# FluxamasynthPhoton.net
KiCad netlist of a schematic drawn in EAGLE
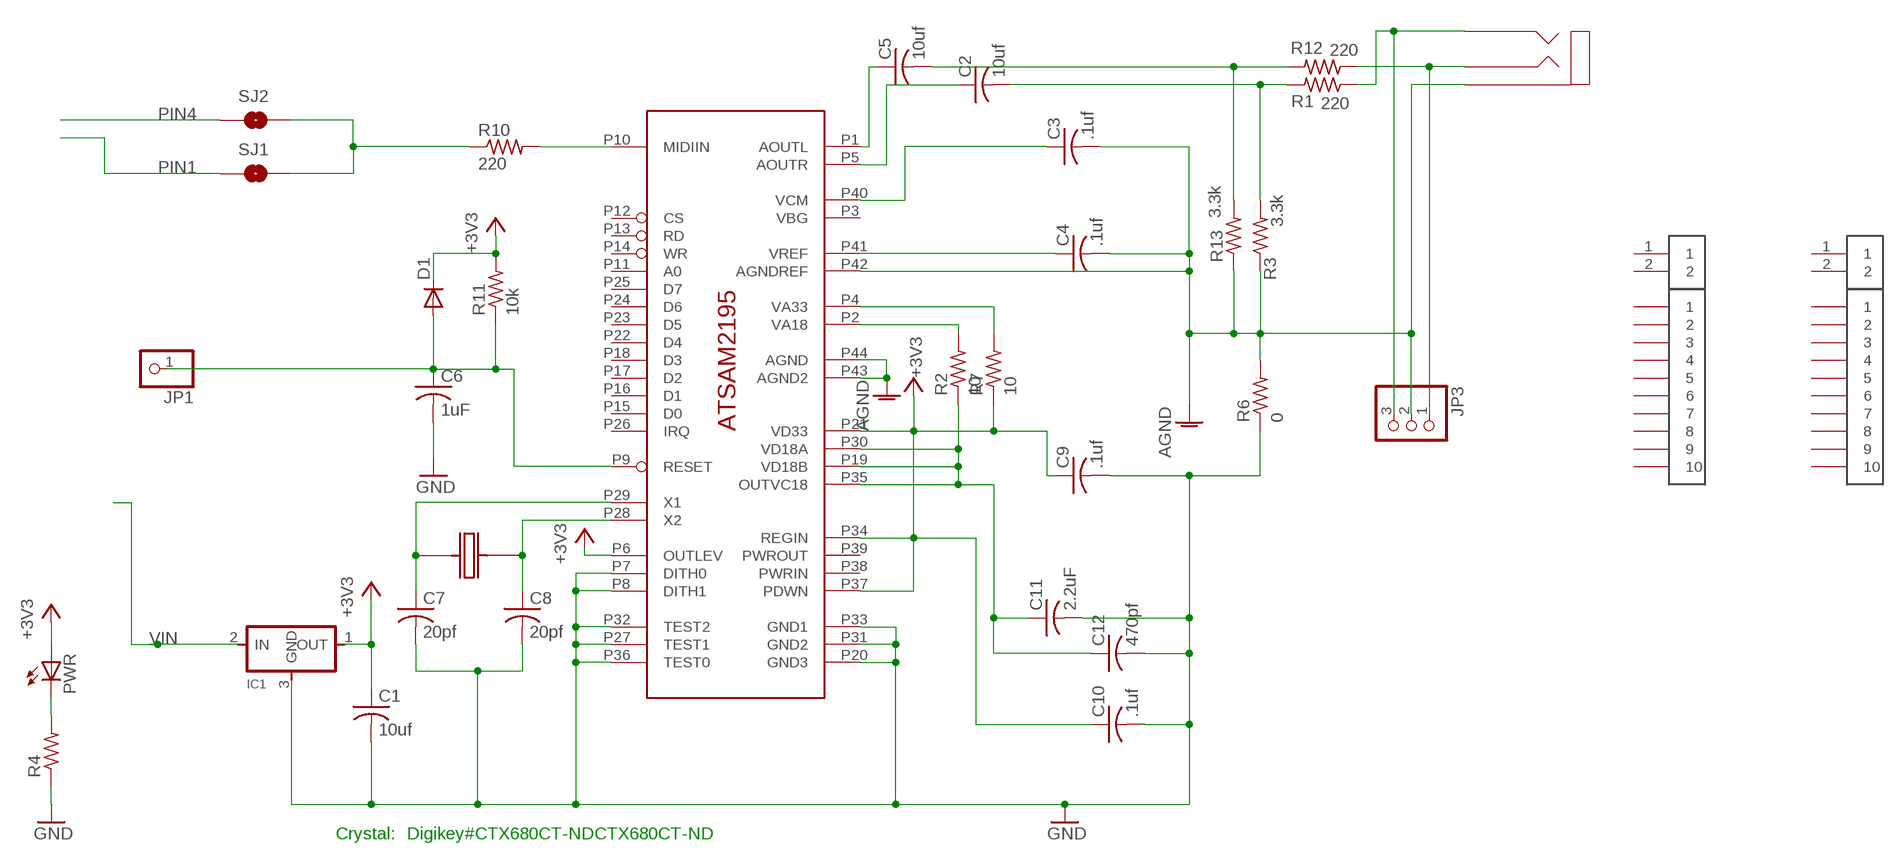
[diagram p0: schematic, sheet 1]

(export (version "E")
  (design (tool "Eeschema 10.0.6"))
  (components
    (comp (ref "C1")
      (value "10uf")
      (footprint "eagle-import:C0603")
      (libsource (lib "eagle-import") (part "C-USC0603"))
    )
    (comp (ref "C2")
      (value "10uf")
      (footprint "eagle-import:C0603")
      (libsource (lib "eagle-import") (part "C-USC0603"))
    )
    (comp (ref "C3")
      (value ".1uf")
      (footprint "eagle-import:C0603")
      (libsource (lib "eagle-import") (part "C-USC0603"))
    )
    (comp (ref "C4")
      (value ".1uf")
      (footprint "eagle-import:C0603")
      (libsource (lib "eagle-import") (part "C-USC0603"))
    )
    (comp (ref "C5")
      (value "10uf")
      (footprint "eagle-import:C0603")
      (libsource (lib "eagle-import") (part "C-USC0603"))
    )
    (comp (ref "C6")
      (value "1uF")
      (footprint "eagle-import:C0603")
      (libsource (lib "eagle-import") (part "C-USC0603"))
    )
    (comp (ref "C7")
      (value "20pf")
      (footprint "eagle-import:C0603K")
      (libsource (lib "eagle-import") (part "C-USC0603K"))
    )
    (comp (ref "C8")
      (value "20pf")
      (footprint "eagle-import:C0603K")
      (libsource (lib "eagle-import") (part "C-USC0603K"))
    )
    (comp (ref "C9")
      (value ".1uf")
      (footprint "eagle-import:C0603")
      (libsource (lib "eagle-import") (part "C-USC0603"))
    )
    (comp (ref "C10")
      (value ".1uf")
      (footprint "eagle-import:C0603")
      (libsource (lib "eagle-import") (part "C-USC0603"))
    )
    (comp (ref "C11")
      (value "2.2uF")
      (footprint "eagle-import:C0603")
      (libsource (lib "eagle-import") (part "C-USC0603"))
    )
    (comp (ref "C12")
      (value "470pf")
      (footprint "eagle-import:C0603")
      (libsource (lib "eagle-import") (part "C-USC0603"))
    )
    (comp (ref "D1")
      (value "DIODESOD123")
      (footprint "eagle-import:SOD123")
      (libsource (lib "eagle-import") (part "DIODESOD123"))
    )
    (comp (ref "IC1")
      (value "REGULATORSOT23")
      (footprint "eagle-import:SOT23")
      (libsource (lib "eagle-import") (part "REGULATORSOT23"))
    )
    (comp (ref "JP1")
      (value "PINHD-1X1")
      (footprint "eagle-import:1X01")
      (libsource (lib "eagle-import") (part "PINHD-1X1"))
    )
    (comp (ref "JP3")
      (value "PINHD-1X3CB")
      (footprint "eagle-import:1X03-CLEANBIG")
      (libsource (lib "eagle-import") (part "PINHD-1X3CB"))
    )
    (comp (ref "PWR")
      (value "LED0603")
      (footprint "eagle-import:LED-0603")
      (libsource (lib "eagle-import") (part "LED0603"))
    )
    (comp (ref "R1")
      (value "220")
      (footprint "eagle-import:R0603")
      (libsource (lib "eagle-import") (part "R-US_R0603"))
    )
    (comp (ref "R2")
      (value "10")
      (footprint "eagle-import:R0603")
      (libsource (lib "eagle-import") (part "R-US_R0603"))
    )
    (comp (ref "R3")
      (value "3.3k")
      (footprint "eagle-import:R0603")
      (libsource (lib "eagle-import") (part "R-US_R0603"))
    )
    (comp (ref "R4")
      (value "R-US_R0603")
      (footprint "eagle-import:R0603")
      (libsource (lib "eagle-import") (part "R-US_R0603"))
    )
    (comp (ref "R6")
      (value "0")
      (footprint "eagle-import:R0603")
      (libsource (lib "eagle-import") (part "R-US_R0603"))
    )
    (comp (ref "R7")
      (value "10")
      (footprint "eagle-import:R0603")
      (libsource (lib "eagle-import") (part "R-US_R0603"))
    )
    (comp (ref "R10")
      (value "220")
      (footprint "eagle-import:R0603")
      (libsource (lib "eagle-import") (part "R-US_R0603"))
    )
    (comp (ref "R11")
      (value "10k")
      (footprint "eagle-import:R0603")
      (libsource (lib "eagle-import") (part "R-US_R0603"))
    )
    (comp (ref "R12")
      (value "220")
      (footprint "eagle-import:R0603")
      (libsource (lib "eagle-import") (part "R-US_R0603"))
    )
    (comp (ref "R13")
      (value "3.3k")
      (footprint "eagle-import:R0603")
      (libsource (lib "eagle-import") (part "R-US_R0603"))
    )
    (comp (ref "SJ1")
      (value "SOLDERJUMPERNO")
      (footprint "eagle-import:SJ_2S-NO")
      (libsource (lib "eagle-import") (part "SOLDERJUMPERNO"))
    )
    (comp (ref "SJ2")
      (value "SOLDERJUMPERNC2")
      (footprint "eagle-import:SJ_2S-NOTRACE")
      (libsource (lib "eagle-import") (part "SOLDERJUMPERNC2"))
    )
    (comp (ref "U$1")
      (value "ATSAM2195")
      (footprint "eagle-import:ATSAM2195")
      (libsource (lib "eagle-import") (part "ATSAM2195"))
    )
    (comp (ref "U$2")
      (value "CRYSTAL_7X5")
      (footprint "eagle-import:CRYSTAL_7X5")
      (libsource (lib "eagle-import") (part "CRYSTAL_7X5"))
    )
    (comp (ref "U$3")
      (value "1X10_CLEAN")
      (footprint "eagle-import:1X10_CLEAN")
      (libsource (lib "eagle-import") (part "1X10_CLEAN"))
    )
    (comp (ref "U$4")
      (value "STEREO_AUDIO_JACK_SMT")
      (footprint "eagle-import:STEREO_AUDIO_JACK_SMT")
      (libsource (lib "eagle-import") (part "STEREO_AUDIO_JACK_SMT"))
    )
    (comp (ref "U$5")
      (value "1X10_CLEAN")
      (footprint "eagle-import:1X10_CLEAN")
      (libsource (lib "eagle-import") (part "1X10_CLEAN"))
    )
    (comp (ref "U$6")
      (value "1X2_CLEAN")
      (footprint "eagle-import:1X2_CLEAN")
      (libsource (lib "eagle-import") (part "1X2_CLEAN"))
    )
    (comp (ref "U$7")
      (value "1X2_CLEAN")
      (footprint "eagle-import:1X2_CLEAN")
      (libsource (lib "eagle-import") (part "1X2_CLEAN"))
    )
  )
  (nets
    (net (code "1") (name "+3V3") (class "Default")
      (node (ref "C1") (pin "1") (pinfunction "1_1") (pintype "passive"))
      (node (ref "C10") (pin "1") (pinfunction "1_1") (pintype "passive"))
      (node (ref "C9") (pin "1") (pinfunction "1_1") (pintype "passive"))
      (node (ref "D1") (pin "CATHODE") (pinfunction "C_CATHODE") (pintype "passive"))
      (node (ref "IC1") (pin "1") (pinfunction "OUT_1") (pintype "bidirectional"))
      (node (ref "PWR") (pin "A") (pinfunction "A_A") (pintype "passive"))
      (node (ref "R11") (pin "2") (pinfunction "2_2") (pintype "passive"))
      (node (ref "R7") (pin "1") (pinfunction "1_1") (pintype "passive"))
      (node (ref "U$1") (pin "P21") (pinfunction "VD33_P21") (pintype "bidirectional"))
      (node (ref "U$1") (pin "P34") (pinfunction "REGIN_P34") (pintype "bidirectional"))
      (node (ref "U$1") (pin "P37") (pinfunction "PDWN_P37") (pintype "bidirectional"))
      (node (ref "U$1") (pin "P6") (pinfunction "OUTLEV_P6") (pintype "bidirectional"))
    )
    (net (code "2") (name "/PIN1") (class "Default")
      (node (ref "SJ1") (pin "1") (pinfunction "1_1") (pintype "passive"))
    )
    (net (code "3") (name "/PIN4") (class "Default")
      (node (ref "SJ2") (pin "1") (pinfunction "1_1") (pintype "passive"))
    )
    (net (code "4") (name "/VIN") (class "Default")
      (node (ref "IC1") (pin "2") (pinfunction "IN_2") (pintype "bidirectional"))
    )
    (net (code "5") (name "AGND") (class "Default")
      (node (ref "C3") (pin "2") (pinfunction "2_2") (pintype "passive"))
      (node (ref "C4") (pin "2") (pinfunction "2_2") (pintype "passive"))
      (node (ref "JP3") (pin "2") (pinfunction "2_2") (pintype "passive"))
      (node (ref "R13") (pin "1") (pinfunction "1_1") (pintype "passive"))
      (node (ref "R3") (pin "1") (pinfunction "1_1") (pintype "passive"))
      (node (ref "R6") (pin "2") (pinfunction "2_2") (pintype "passive"))
      (node (ref "U$1") (pin "P42") (pinfunction "AGNDREF_P42") (pintype "bidirectional"))
      (node (ref "U$1") (pin "P43") (pinfunction "AGND2_P43") (pintype "bidirectional"))
      (node (ref "U$1") (pin "P44") (pinfunction "AGND_P44") (pintype "bidirectional"))
      (node (ref "U$4") (pin "P$1") (pinfunction "SHIELD_P$1") (pintype "bidirectional"))
    )
    (net (code "6") (name "GND") (class "Default")
      (node (ref "C1") (pin "2") (pinfunction "2_2") (pintype "passive"))
      (node (ref "C10") (pin "2") (pinfunction "2_2") (pintype "passive"))
      (node (ref "C11") (pin "2") (pinfunction "2_2") (pintype "passive"))
      (node (ref "C12") (pin "2") (pinfunction "2_2") (pintype "passive"))
      (node (ref "C6") (pin "2") (pinfunction "2_2") (pintype "passive"))
      (node (ref "C7") (pin "2") (pinfunction "2_2") (pintype "passive"))
      (node (ref "C8") (pin "2") (pinfunction "2_2") (pintype "passive"))
      (node (ref "C9") (pin "2") (pinfunction "2_2") (pintype "passive"))
      (node (ref "IC1") (pin "3") (pinfunction "GND_3") (pintype "bidirectional"))
      (node (ref "R4") (pin "1") (pinfunction "1_1") (pintype "passive"))
      (node (ref "R6") (pin "1") (pinfunction "1_1") (pintype "passive"))
      (node (ref "U$1") (pin "P20") (pinfunction "GND3_P20") (pintype "bidirectional"))
      (node (ref "U$1") (pin "P27") (pinfunction "TEST1_P27") (pintype "bidirectional"))
      (node (ref "U$1") (pin "P31") (pinfunction "GND2_P31") (pintype "bidirectional"))
      (node (ref "U$1") (pin "P32") (pinfunction "TEST2_P32") (pintype "bidirectional"))
      (node (ref "U$1") (pin "P33") (pinfunction "GND1_P33") (pintype "bidirectional"))
      (node (ref "U$1") (pin "P36") (pinfunction "TEST0_P36") (pintype "bidirectional"))
      (node (ref "U$1") (pin "P7") (pinfunction "DITH0_P7") (pintype "bidirectional"))
      (node (ref "U$1") (pin "P8") (pinfunction "DITH1_P8") (pintype "bidirectional"))
    )
    (net (code "7") (name "Net-(C2-Pad2)") (class "Default")
      (node (ref "C2") (pin "2") (pinfunction "2_2") (pintype "passive"))
      (node (ref "R1") (pin "2") (pinfunction "2_2") (pintype "passive"))
      (node (ref "R3") (pin "2") (pinfunction "2_2") (pintype "passive"))
    )
    (net (code "8") (name "Net-(C5-Pad2)") (class "Default")
      (node (ref "C5") (pin "2") (pinfunction "2_2") (pintype "passive"))
      (node (ref "R12") (pin "2") (pinfunction "2_2") (pintype "passive"))
      (node (ref "R13") (pin "2") (pinfunction "2_2") (pintype "passive"))
    )
    (net (code "9") (name "Net-(D1-A)") (class "Default")
      (node (ref "C6") (pin "1") (pinfunction "1_1") (pintype "passive"))
      (node (ref "D1") (pin "ANODE") (pinfunction "A_ANODE") (pintype "passive"))
      (node (ref "JP1") (pin "1") (pinfunction "1_1") (pintype "passive"))
      (node (ref "R11") (pin "1") (pinfunction "1_1") (pintype "passive"))
      (node (ref "U$1") (pin "P9") (pinfunction "RESET_P9") (pintype "bidirectional"))
    )
    (net (code "10") (name "Net-(PWR-PadC)") (class "Default")
      (node (ref "PWR") (pin "C") (pinfunction "C_C") (pintype "passive"))
      (node (ref "R4") (pin "2") (pinfunction "2_2") (pintype "passive"))
    )
    (net (code "11") (name "Net-(R10-Pad1)") (class "Default")
      (node (ref "R10") (pin "1") (pinfunction "1_1") (pintype "passive"))
      (node (ref "SJ1") (pin "2") (pinfunction "2_2") (pintype "passive"))
      (node (ref "SJ2") (pin "2") (pinfunction "2_2") (pintype "passive"))
    )
    (net (code "12") (name "Net-(U$1-AOUTL)") (class "Default")
      (node (ref "C5") (pin "1") (pinfunction "1_1") (pintype "passive"))
      (node (ref "U$1") (pin "P1") (pinfunction "AOUTL_P1") (pintype "bidirectional"))
    )
    (net (code "13") (name "Net-(U$1-AOUTR)") (class "Default")
      (node (ref "C2") (pin "1") (pinfunction "1_1") (pintype "passive"))
      (node (ref "U$1") (pin "P5") (pinfunction "AOUTR_P5") (pintype "bidirectional"))
    )
    (net (code "14") (name "Net-(U$1-MIDIIN)") (class "Default")
      (node (ref "R10") (pin "2") (pinfunction "2_2") (pintype "passive"))
      (node (ref "U$1") (pin "P10") (pinfunction "MIDIIN_P10") (pintype "bidirectional"))
    )
    (net (code "15") (name "Net-(U$1-OUTVC18)") (class "Default")
      (node (ref "C11") (pin "1") (pinfunction "1_1") (pintype "passive"))
      (node (ref "C12") (pin "1") (pinfunction "1_1") (pintype "passive"))
      (node (ref "R2") (pin "1") (pinfunction "1_1") (pintype "passive"))
      (node (ref "U$1") (pin "P19") (pinfunction "VD18B_P19") (pintype "bidirectional"))
      (node (ref "U$1") (pin "P30") (pinfunction "VD18A_P30") (pintype "bidirectional"))
      (node (ref "U$1") (pin "P35") (pinfunction "OUTVC18_P35") (pintype "bidirectional"))
    )
    (net (code "16") (name "Net-(U$1-VA18)") (class "Default")
      (node (ref "R2") (pin "2") (pinfunction "2_2") (pintype "passive"))
      (node (ref "U$1") (pin "P2") (pinfunction "VA18_P2") (pintype "bidirectional"))
    )
    (net (code "17") (name "Net-(U$1-VA33)") (class "Default")
      (node (ref "R7") (pin "2") (pinfunction "2_2") (pintype "passive"))
      (node (ref "U$1") (pin "P4") (pinfunction "VA33_P4") (pintype "bidirectional"))
    )
    (net (code "18") (name "Net-(U$1-VCM)") (class "Default")
      (node (ref "C3") (pin "1") (pinfunction "1_1") (pintype "passive"))
      (node (ref "U$1") (pin "P40") (pinfunction "VCM_P40") (pintype "bidirectional"))
    )
    (net (code "19") (name "Net-(U$1-VREF)") (class "Default")
      (node (ref "C4") (pin "1") (pinfunction "1_1") (pintype "passive"))
      (node (ref "U$1") (pin "P41") (pinfunction "VREF_P41") (pintype "bidirectional"))
    )
    (net (code "20") (name "Net-(U$1-X1)") (class "Default")
      (node (ref "C7") (pin "1") (pinfunction "1_1") (pintype "passive"))
      (node (ref "U$1") (pin "P29") (pinfunction "X1_P29") (pintype "bidirectional"))
      (node (ref "U$2") (pin "P$1") (pinfunction "P$1_P$1") (pintype "bidirectional"))
    )
    (net (code "21") (name "Net-(U$1-X2)") (class "Default")
      (node (ref "C8") (pin "1") (pinfunction "1_1") (pintype "passive"))
      (node (ref "U$1") (pin "P28") (pinfunction "X2_P28") (pintype "bidirectional"))
      (node (ref "U$2") (pin "P$3") (pinfunction "P$2_P$3") (pintype "bidirectional"))
    )
    (net (code "22") (name "Net-(U$4-RING)") (class "Default")
      (node (ref "JP3") (pin "1") (pinfunction "1_1") (pintype "passive"))
      (node (ref "R12") (pin "1") (pinfunction "1_1") (pintype "passive"))
      (node (ref "U$4") (pin "P$3") (pinfunction "RING_P$3") (pintype "bidirectional"))
    )
    (net (code "23") (name "Net-(U$4-TIP)") (class "Default")
      (node (ref "JP3") (pin "3") (pinfunction "3_3") (pintype "passive"))
      (node (ref "R1") (pin "1") (pinfunction "1_1") (pintype "passive"))
      (node (ref "U$4") (pin "P$2") (pinfunction "TIP_P$2") (pintype "bidirectional"))
    )
    (net (code "24") (name "unconnected-(U$1-A0-PadP11)") (class "Default")
      (node (ref "U$1") (pin "P11") (pinfunction "A0_P11") (pintype "bidirectional"))
    )
    (net (code "25") (name "unconnected-(U$1-CS-PadP12)") (class "Default")
      (node (ref "U$1") (pin "P12") (pinfunction "CS_P12") (pintype "bidirectional"))
    )
    (net (code "26") (name "unconnected-(U$1-D0-PadP15)") (class "Default")
      (node (ref "U$1") (pin "P15") (pinfunction "D0_P15") (pintype "bidirectional"))
    )
    (net (code "27") (name "unconnected-(U$1-D1-PadP16)") (class "Default")
      (node (ref "U$1") (pin "P16") (pinfunction "D1_P16") (pintype "bidirectional"))
    )
    (net (code "28") (name "unconnected-(U$1-D2-PadP17)") (class "Default")
      (node (ref "U$1") (pin "P17") (pinfunction "D2_P17") (pintype "bidirectional"))
    )
    (net (code "29") (name "unconnected-(U$1-D3-PadP18)") (class "Default")
      (node (ref "U$1") (pin "P18") (pinfunction "D3_P18") (pintype "bidirectional"))
    )
    (net (code "30") (name "unconnected-(U$1-D4-PadP22)") (class "Default")
      (node (ref "U$1") (pin "P22") (pinfunction "D4_P22") (pintype "bidirectional"))
    )
    (net (code "31") (name "unconnected-(U$1-D5-PadP23)") (class "Default")
      (node (ref "U$1") (pin "P23") (pinfunction "D5_P23") (pintype "bidirectional"))
    )
    (net (code "32") (name "unconnected-(U$1-D6-PadP24)") (class "Default")
      (node (ref "U$1") (pin "P24") (pinfunction "D6_P24") (pintype "bidirectional"))
    )
    (net (code "33") (name "unconnected-(U$1-D7-PadP25)") (class "Default")
      (node (ref "U$1") (pin "P25") (pinfunction "D7_P25") (pintype "bidirectional"))
    )
    (net (code "34") (name "unconnected-(U$1-IRQ-PadP26)") (class "Default")
      (node (ref "U$1") (pin "P26") (pinfunction "IRQ_P26") (pintype "bidirectional"))
    )
    (net (code "35") (name "unconnected-(U$1-PWRIN-PadP38)") (class "Default")
      (node (ref "U$1") (pin "P38") (pinfunction "PWRIN_P38") (pintype "bidirectional"))
    )
    (net (code "36") (name "unconnected-(U$1-PWROUT-PadP39)") (class "Default")
      (node (ref "U$1") (pin "P39") (pinfunction "PWROUT_P39") (pintype "bidirectional"))
    )
    (net (code "37") (name "unconnected-(U$1-RD-PadP13)") (class "Default")
      (node (ref "U$1") (pin "P13") (pinfunction "RD_P13") (pintype "bidirectional"))
    )
    (net (code "38") (name "unconnected-(U$1-VBG-PadP3)") (class "Default")
      (node (ref "U$1") (pin "P3") (pinfunction "VBG_P3") (pintype "bidirectional"))
    )
    (net (code "39") (name "unconnected-(U$1-WR-PadP14)") (class "Default")
      (node (ref "U$1") (pin "P14") (pinfunction "WR_P14") (pintype "bidirectional"))
    )
    (net (code "40") (name "unconnected-(U$3-1-PadP$1)") (class "Default")
      (node (ref "U$3") (pin "P$1") (pinfunction "1_P$1") (pintype "bidirectional"))
    )
    (net (code "41") (name "unconnected-(U$3-2-PadP$2)") (class "Default")
      (node (ref "U$3") (pin "P$2") (pinfunction "2_P$2") (pintype "bidirectional"))
    )
    (net (code "42") (name "unconnected-(U$3-3-PadP$3)") (class "Default")
      (node (ref "U$3") (pin "P$3") (pinfunction "3_P$3") (pintype "bidirectional"))
    )
    (net (code "43") (name "unconnected-(U$3-4-PadP$4)") (class "Default")
      (node (ref "U$3") (pin "P$4") (pinfunction "4_P$4") (pintype "bidirectional"))
    )
    (net (code "44") (name "unconnected-(U$3-5-PadP$5)") (class "Default")
      (node (ref "U$3") (pin "P$5") (pinfunction "5_P$5") (pintype "bidirectional"))
    )
    (net (code "45") (name "unconnected-(U$3-6-PadP$6)") (class "Default")
      (node (ref "U$3") (pin "P$6") (pinfunction "6_P$6") (pintype "bidirectional"))
    )
    (net (code "46") (name "unconnected-(U$3-7-PadP$7)") (class "Default")
      (node (ref "U$3") (pin "P$7") (pinfunction "7_P$7") (pintype "bidirectional"))
    )
    (net (code "47") (name "unconnected-(U$3-8-PadP$8)") (class "Default")
      (node (ref "U$3") (pin "P$8") (pinfunction "8_P$8") (pintype "bidirectional"))
    )
    (net (code "48") (name "unconnected-(U$3-9-PadP$9)") (class "Default")
      (node (ref "U$3") (pin "P$9") (pinfunction "9_P$9") (pintype "bidirectional"))
    )
    (net (code "49") (name "unconnected-(U$3-10-PadP$10)") (class "Default")
      (node (ref "U$3") (pin "P$10") (pinfunction "10_P$10") (pintype "bidirectional"))
    )
    (net (code "50") (name "unconnected-(U$5-1-PadP$1)") (class "Default")
      (node (ref "U$5") (pin "P$1") (pinfunction "1_P$1") (pintype "bidirectional"))
    )
    (net (code "51") (name "unconnected-(U$5-2-PadP$2)") (class "Default")
      (node (ref "U$5") (pin "P$2") (pinfunction "2_P$2") (pintype "bidirectional"))
    )
    (net (code "52") (name "unconnected-(U$5-3-PadP$3)") (class "Default")
      (node (ref "U$5") (pin "P$3") (pinfunction "3_P$3") (pintype "bidirectional"))
    )
    (net (code "53") (name "unconnected-(U$5-4-PadP$4)") (class "Default")
      (node (ref "U$5") (pin "P$4") (pinfunction "4_P$4") (pintype "bidirectional"))
    )
    (net (code "54") (name "unconnected-(U$5-5-PadP$5)") (class "Default")
      (node (ref "U$5") (pin "P$5") (pinfunction "5_P$5") (pintype "bidirectional"))
    )
    (net (code "55") (name "unconnected-(U$5-6-PadP$6)") (class "Default")
      (node (ref "U$5") (pin "P$6") (pinfunction "6_P$6") (pintype "bidirectional"))
    )
    (net (code "56") (name "unconnected-(U$5-7-PadP$7)") (class "Default")
      (node (ref "U$5") (pin "P$7") (pinfunction "7_P$7") (pintype "bidirectional"))
    )
    (net (code "57") (name "unconnected-(U$5-8-PadP$8)") (class "Default")
      (node (ref "U$5") (pin "P$8") (pinfunction "8_P$8") (pintype "bidirectional"))
    )
    (net (code "58") (name "unconnected-(U$5-9-PadP$9)") (class "Default")
      (node (ref "U$5") (pin "P$9") (pinfunction "9_P$9") (pintype "bidirectional"))
    )
    (net (code "59") (name "unconnected-(U$5-10-PadP$10)") (class "Default")
      (node (ref "U$5") (pin "P$10") (pinfunction "10_P$10") (pintype "bidirectional"))
    )
    (net (code "60") (name "unconnected-(U$6-Pad1)") (class "Default")
      (node (ref "U$6") (pin "1") (pinfunction "1_1") (pintype "bidirectional"))
    )
    (net (code "61") (name "unconnected-(U$6-Pad2)") (class "Default")
      (node (ref "U$6") (pin "2") (pinfunction "2_2") (pintype "bidirectional"))
    )
    (net (code "62") (name "unconnected-(U$7-Pad1)") (class "Default")
      (node (ref "U$7") (pin "1") (pinfunction "1_1") (pintype "bidirectional"))
    )
    (net (code "63") (name "unconnected-(U$7-Pad2)") (class "Default")
      (node (ref "U$7") (pin "2") (pinfunction "2_2") (pintype "bidirectional"))
    )
  )
)
